# power_mux-v6.net
KiCad netlist of a schematic drawn in EAGLE
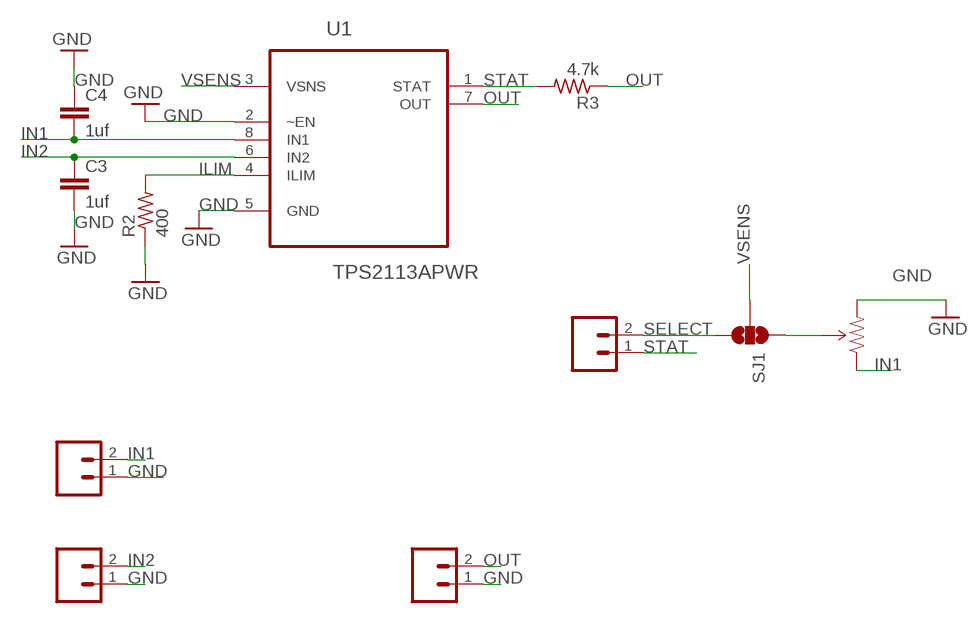
[diagram p0: schematic, sheet 1]

(export (version "E")
  (design (tool "Eeschema 10.0.6"))
  (components
    (comp (ref "C3")
      (value "1uf")
      (footprint "eagle-import:0402-CAP")
      (libsource (lib "eagle-import") (part "CAP0402-CAP"))
    )
    (comp (ref "C4")
      (value "1uf")
      (footprint "eagle-import:0402-CAP")
      (libsource (lib "eagle-import") (part "CAP0402-CAP"))
    )
    (comp (ref "JP3")
      (value "M021X02_NO_SILK")
      (footprint "eagle-import:1X02_NO_SILK")
      (libsource (lib "eagle-import") (part "M021X02_NO_SILK"))
    )
    (comp (ref "JP4")
      (value "M021X02_NO_SILK")
      (footprint "eagle-import:1X02_NO_SILK")
      (libsource (lib "eagle-import") (part "M021X02_NO_SILK"))
    )
    (comp (ref "JP5")
      (value "M021X02_NO_SILK")
      (footprint "eagle-import:1X02_NO_SILK")
      (libsource (lib "eagle-import") (part "M021X02_NO_SILK"))
    )
    (comp (ref "JP6")
      (value "M021X02_NO_SILK")
      (footprint "eagle-import:1X02_NO_SILK")
      (libsource (lib "eagle-import") (part "M021X02_NO_SILK"))
    )
    (comp (ref "R1")
      (value "TRIMPOT-PTH-KNOB")
      (footprint "eagle-import:3386U")
      (libsource (lib "eagle-import") (part "TRIMPOT-PTH-KNOB"))
    )
    (comp (ref "R2")
      (value "400")
      (footprint "eagle-import:R0402")
      (libsource (lib "eagle-import") (part "R-US_R0402"))
    )
    (comp (ref "R3")
      (value "4.7k")
      (footprint "eagle-import:R0402")
      (libsource (lib "eagle-import") (part "R-US_R0402"))
    )
    (comp (ref "SJ1")
      (value "SOLDERJUMPER_2WAYPASTE1&2")
      (footprint "eagle-import:SJ_3_PASTE1&2")
      (libsource (lib "eagle-import") (part "SOLDERJUMPER_2WAYPASTE1&2"))
    )
    (comp (ref "U1")
      (value "TPS2113APWR")
      (footprint "eagle-import:SOP65P640X120-8N")
      (libsource (lib "eagle-import") (part "TPS2113APWR"))
    )
  )
  (nets
    (net (code "1") (name "/ILIM") (class "Default")
      (node (ref "R2") (pin "2") (pinfunction "2_2") (pintype "passive"))
      (node (ref "U1") (pin "4") (pinfunction "ILIM_4") (pintype "input"))
    )
    (net (code "2") (name "/IN1") (class "Default")
      (node (ref "C4") (pin "2") (pinfunction "2_2") (pintype "passive"))
      (node (ref "JP3") (pin "2") (pinfunction "2_2") (pintype "passive"))
      (node (ref "R1") (pin "1") (pinfunction "CCW_1") (pintype "passive"))
      (node (ref "U1") (pin "8") (pinfunction "IN1_8") (pintype "input"))
    )
    (net (code "3") (name "/IN2") (class "Default")
      (node (ref "C3") (pin "1") (pinfunction "1_1") (pintype "passive"))
      (node (ref "JP4") (pin "2") (pinfunction "2_2") (pintype "passive"))
      (node (ref "U1") (pin "6") (pinfunction "IN2_6") (pintype "input"))
    )
    (net (code "4") (name "/OUT") (class "Default")
      (node (ref "JP6") (pin "2") (pinfunction "2_2") (pintype "passive"))
      (node (ref "R3") (pin "1") (pinfunction "1_1") (pintype "passive"))
      (node (ref "U1") (pin "7") (pinfunction "OUT_7") (pintype "output"))
    )
    (net (code "5") (name "/SELECT") (class "Default")
      (node (ref "JP5") (pin "2") (pinfunction "2_2") (pintype "passive"))
      (node (ref "SJ1") (pin "3") (pinfunction "3_3") (pintype "passive"))
    )
    (net (code "6") (name "/STAT") (class "Default")
      (node (ref "JP5") (pin "1") (pinfunction "1_1") (pintype "passive"))
      (node (ref "R3") (pin "2") (pinfunction "2_2") (pintype "passive"))
      (node (ref "U1") (pin "1") (pinfunction "STAT_1") (pintype "output"))
    )
    (net (code "7") (name "/VSENS") (class "Default")
      (node (ref "SJ1") (pin "2") (pinfunction "2_2") (pintype "passive"))
      (node (ref "U1") (pin "3") (pinfunction "VSNS_3") (pintype "power_in"))
    )
    (net (code "8") (name "GND") (class "Default")
      (node (ref "C3") (pin "2") (pinfunction "2_2") (pintype "passive"))
      (node (ref "C4") (pin "1") (pinfunction "1_1") (pintype "passive"))
      (node (ref "JP3") (pin "1") (pinfunction "1_1") (pintype "passive"))
      (node (ref "JP4") (pin "1") (pinfunction "1_1") (pintype "passive"))
      (node (ref "JP6") (pin "1") (pinfunction "1_1") (pintype "passive"))
      (node (ref "R1") (pin "3") (pinfunction "CW_3") (pintype "passive"))
      (node (ref "R2") (pin "1") (pinfunction "1_1") (pintype "passive"))
      (node (ref "U1") (pin "2") (pinfunction "~{EN}_2") (pintype "input"))
      (node (ref "U1") (pin "5") (pinfunction "GND_5") (pintype "passive"))
    )
    (net (code "9") (name "Net-(R1-WIPER)") (class "Default")
      (node (ref "R1") (pin "2") (pinfunction "WIPER_2") (pintype "passive"))
      (node (ref "SJ1") (pin "1") (pinfunction "1_1") (pintype "passive"))
    )
  )
)
